# PowerConversion.net
KiCad netlist of a schematic drawn in Altium Designer
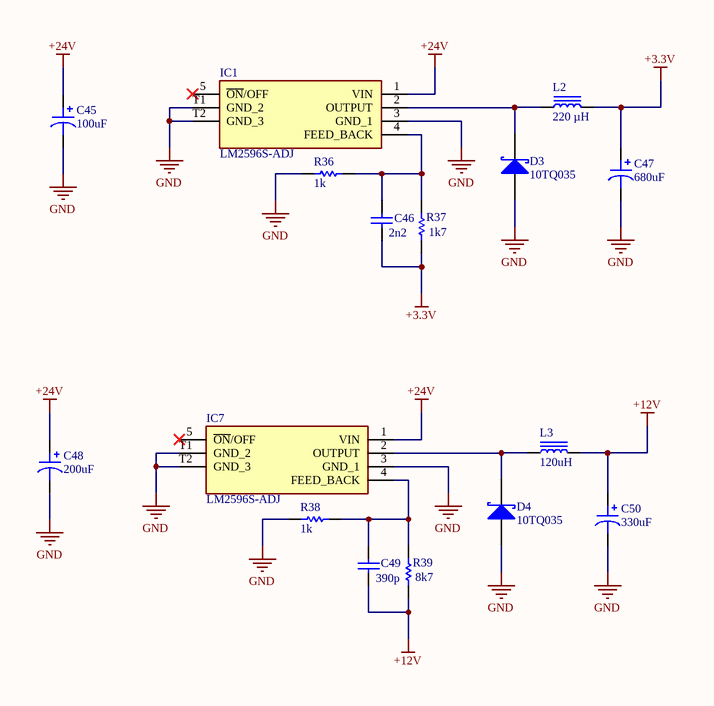
[diagram p0: PowerConversion.SchDoc]

(export (version "E")
  (design (tool "Eeschema 10.0.6"))
  (components
    (comp (ref "C45")
      (value "100uF")
      (footprint "CAP ALSMD 8.3MM H10.5MM")
      (description "CAP ALUM 100UF 20% 35V SMD")
      (fields (field (name "PART NUMBER") "UUX1V101MNL6GS") (field (name "MANUFACTURER") "Nichicon"))
      (libsource (lib "Celestial Altium Library - altium_library") (part "Polarised Capacitor"))
    )
    (comp (ref "C46")
      (value "2n2")
      (footprint "RAD-0.3")
      (description "Capacitor")
      (fields (field (name "Comment") "Cap") (field (name "PUBLISHER") "Altium Limited"))
      (libsource (lib "Miscellaneous Devices") (part "Cap"))
    )
    (comp (ref "C47")
      (value "680uF")
      (footprint "CAP ALSMD 8.3MM H10.5MM")
      (description "CAP ALUM 100UF 20% 35V SMD")
      (fields (field (name "PART NUMBER") "UUX1V101MNL6GS") (field (name "MANUFACTURER") "Nichicon"))
      (libsource (lib "Celestial Altium Library - altium_library") (part "Polarised Capacitor"))
    )
    (comp (ref "C48")
      (value "200uF")
      (footprint "CAP ALSMD 8.3MM H10.5MM")
      (description "CAP ALUM 100UF 20% 35V SMD")
      (fields (field (name "PART NUMBER") "UUX1V101MNL6GS") (field (name "MANUFACTURER") "Nichicon"))
      (libsource (lib "Celestial Altium Library - altium_library") (part "Polarised Capacitor"))
    )
    (comp (ref "C49")
      (value "390p")
      (footprint "RAD-0.3")
      (description "Capacitor")
      (fields (field (name "Comment") "Cap") (field (name "PUBLISHER") "Altium Limited"))
      (libsource (lib "Miscellaneous Devices") (part "Cap"))
    )
    (comp (ref "C50")
      (value "330uF")
      (footprint "CAP ALSMD 8.3MM H10.5MM")
      (description "CAP ALUM 100UF 20% 35V SMD")
      (fields (field (name "PART NUMBER") "UUX1V101MNL6GS") (field (name "MANUFACTURER") "Nichicon"))
      (libsource (lib "Celestial Altium Library - altium_library") (part "Polarised Capacitor"))
    )
    (comp (ref "D3")
      (value "10TQ035")
      (footprint "TO-220AC")
      (description "Schottky Rectifier")
      (fields (field (name "PUBLISHER") "Altium Limited"))
      (libsource (lib "Miscellaneous Devices") (part "Diode 10TQ035"))
    )
    (comp (ref "D4")
      (value "10TQ035")
      (footprint "TO-220AC")
      (description "Schottky Rectifier")
      (fields (field (name "PUBLISHER") "Altium Limited"))
      (libsource (lib "Miscellaneous Devices") (part "Diode 10TQ035"))
    )
    (comp (ref "IC1")
      (value "LM2596S-ADJ")
      (footprint "SamacSys:LM2596SXADJ")
      (description "Integrated Circuit")
      (fields (field (name "MOUSER PART NUMBER") "926-LM2596S-ADJ"))
      (libsource (lib "*") (part "LM2596S-ADJ"))
    )
    (comp (ref "IC7")
      (value "LM2596S-ADJ")
      (footprint "SamacSys:LM2596SXADJ")
      (description "Integrated Circuit")
      (fields (field (name "MOUSER PART NUMBER") "926-LM2596S-ADJ"))
      (libsource (lib "*") (part "LM2596S-ADJ"))
    )
    (comp (ref "L2")
      (value "220 µH")
      (footprint "WURTH WE-PD 1260")
      (description "FIXED IND 220UH 960MA 400MOHM SM")
      (fields (field (name "PART NUMBER") "744771220") (field (name "MANUFACTURER") "Würth Elektronik"))
      (libsource (lib "Celestial Altium Library - altium_library") (part "Inductor"))
    )
    (comp (ref "L3")
      (value "120uH")
      (footprint "WURTH WE-PD 1260")
      (description "FIXED IND 220UH 960MA 400MOHM SM")
      (fields (field (name "PART NUMBER") "744771220") (field (name "MANUFACTURER") "Würth Elektronik"))
      (libsource (lib "Celestial Altium Library - altium_library") (part "Inductor"))
    )
    (comp (ref "R36")
      (value "1k")
      (footprint "AXIAL-0.3")
      (description "Resistor")
      (fields (field (name "Comment") "Res1") (field (name "PUBLISHER") "Altium Limited"))
      (libsource (lib "Miscellaneous Devices") (part "Res1"))
    )
    (comp (ref "R37")
      (value "1k7")
      (footprint "AXIAL-0.3")
      (description "Resistor")
      (fields (field (name "Comment") "Res1") (field (name "PUBLISHER") "Altium Limited"))
      (libsource (lib "Miscellaneous Devices") (part "Res1"))
    )
    (comp (ref "R38")
      (value "1k")
      (footprint "AXIAL-0.3")
      (description "Resistor")
      (fields (field (name "Comment") "Res1") (field (name "PUBLISHER") "Altium Limited"))
      (libsource (lib "Miscellaneous Devices") (part "Res1"))
    )
    (comp (ref "R39")
      (value "8k7")
      (footprint "AXIAL-0.3")
      (description "Resistor")
      (fields (field (name "Comment") "Res1") (field (name "PUBLISHER") "Altium Limited"))
      (libsource (lib "Miscellaneous Devices") (part "Res1"))
    )
  )
  (nets
    (net (code "1") (name "+3.3V") (class "Default")
      (node (ref "C46") (pin "1") (pinfunction "1_1") (pintype "passive"))
      (node (ref "C47") (pin "1") (pinfunction "1_1") (pintype "passive"))
      (node (ref "L2") (pin "2") (pinfunction "2_2") (pintype "passive"))
      (node (ref "R37") (pin "1") (pinfunction "1_1") (pintype "passive"))
    )
    (net (code "2") (name "+12V") (class "Default")
      (node (ref "C49") (pin "1") (pinfunction "1_1") (pintype "passive"))
      (node (ref "C50") (pin "1") (pinfunction "1_1") (pintype "passive"))
      (node (ref "L3") (pin "2") (pinfunction "2_2") (pintype "passive"))
      (node (ref "R39") (pin "1") (pinfunction "1_1") (pintype "passive"))
    )
    (net (code "3") (name "+24V") (class "Default")
      (node (ref "C45") (pin "1") (pinfunction "1_1") (pintype "passive"))
      (node (ref "C48") (pin "1") (pinfunction "1_1") (pintype "passive"))
      (node (ref "IC1") (pin "1") (pinfunction "VIN_1") (pintype "passive"))
      (node (ref "IC7") (pin "1") (pinfunction "VIN_1") (pintype "passive"))
    )
    (net (code "4") (name "GND") (class "Default")
      (node (ref "C45") (pin "2") (pinfunction "2_2") (pintype "passive"))
      (node (ref "C47") (pin "2") (pinfunction "2_2") (pintype "passive"))
      (node (ref "C48") (pin "2") (pinfunction "2_2") (pintype "passive"))
      (node (ref "C50") (pin "2") (pinfunction "2_2") (pintype "passive"))
      (node (ref "D3") (pin "3") (pinfunction "A_3") (pintype "passive"))
      (node (ref "D4") (pin "3") (pinfunction "A_3") (pintype "passive"))
      (node (ref "IC1") (pin "3") (pinfunction "GND_1_3") (pintype "passive"))
      (node (ref "IC1") (pin "T1") (pinfunction "GND_2_T1") (pintype "passive"))
      (node (ref "IC1") (pin "T2") (pinfunction "GND_3_T2") (pintype "passive"))
      (node (ref "IC7") (pin "3") (pinfunction "GND_1_3") (pintype "passive"))
      (node (ref "IC7") (pin "T1") (pinfunction "GND_2_T1") (pintype "passive"))
      (node (ref "IC7") (pin "T2") (pinfunction "GND_3_T2") (pintype "passive"))
      (node (ref "R36") (pin "2") (pinfunction "2_2") (pintype "passive"))
      (node (ref "R38") (pin "2") (pinfunction "2_2") (pintype "passive"))
    )
    (net (code "5") (name "Net-(D3-K)") (class "Default")
      (node (ref "D3") (pin "1") (pinfunction "K_1") (pintype "passive"))
      (node (ref "IC1") (pin "2") (pinfunction "OUTPUT_2") (pintype "passive"))
      (node (ref "L2") (pin "1") (pinfunction "1_1") (pintype "passive"))
    )
    (net (code "6") (name "Net-(D4-K)") (class "Default")
      (node (ref "D4") (pin "1") (pinfunction "K_1") (pintype "passive"))
      (node (ref "IC7") (pin "2") (pinfunction "OUTPUT_2") (pintype "passive"))
      (node (ref "L3") (pin "1") (pinfunction "1_1") (pintype "passive"))
    )
    (net (code "7") (name "Net-(IC1-FEED_BACK)") (class "Default")
      (node (ref "C46") (pin "2") (pinfunction "2_2") (pintype "passive"))
      (node (ref "IC1") (pin "4") (pinfunction "FEED_BACK_4") (pintype "passive"))
      (node (ref "R36") (pin "1") (pinfunction "1_1") (pintype "passive"))
      (node (ref "R37") (pin "2") (pinfunction "2_2") (pintype "passive"))
    )
    (net (code "8") (name "Net-(IC7-FEED_BACK)") (class "Default")
      (node (ref "C49") (pin "2") (pinfunction "2_2") (pintype "passive"))
      (node (ref "IC7") (pin "4") (pinfunction "FEED_BACK_4") (pintype "passive"))
      (node (ref "R38") (pin "1") (pinfunction "1_1") (pintype "passive"))
      (node (ref "R39") (pin "2") (pinfunction "2_2") (pintype "passive"))
    )
    (net (code "9") (name "unconnected-(IC1-~{ON}{slash}OFF-Pad5)") (class "Default")
      (node (ref "IC1") (pin "5") (pinfunction "~{ON}/OFF_5") (pintype "passive+no_connect"))
    )
    (net (code "10") (name "unconnected-(IC7-~{ON}{slash}OFF-Pad5)") (class "Default")
      (node (ref "IC7") (pin "5") (pinfunction "~{ON}/OFF_5") (pintype "passive+no_connect"))
    )
  )
)
